# GyroDrive.net
KiCad netlist of a schematic drawn in EAGLE
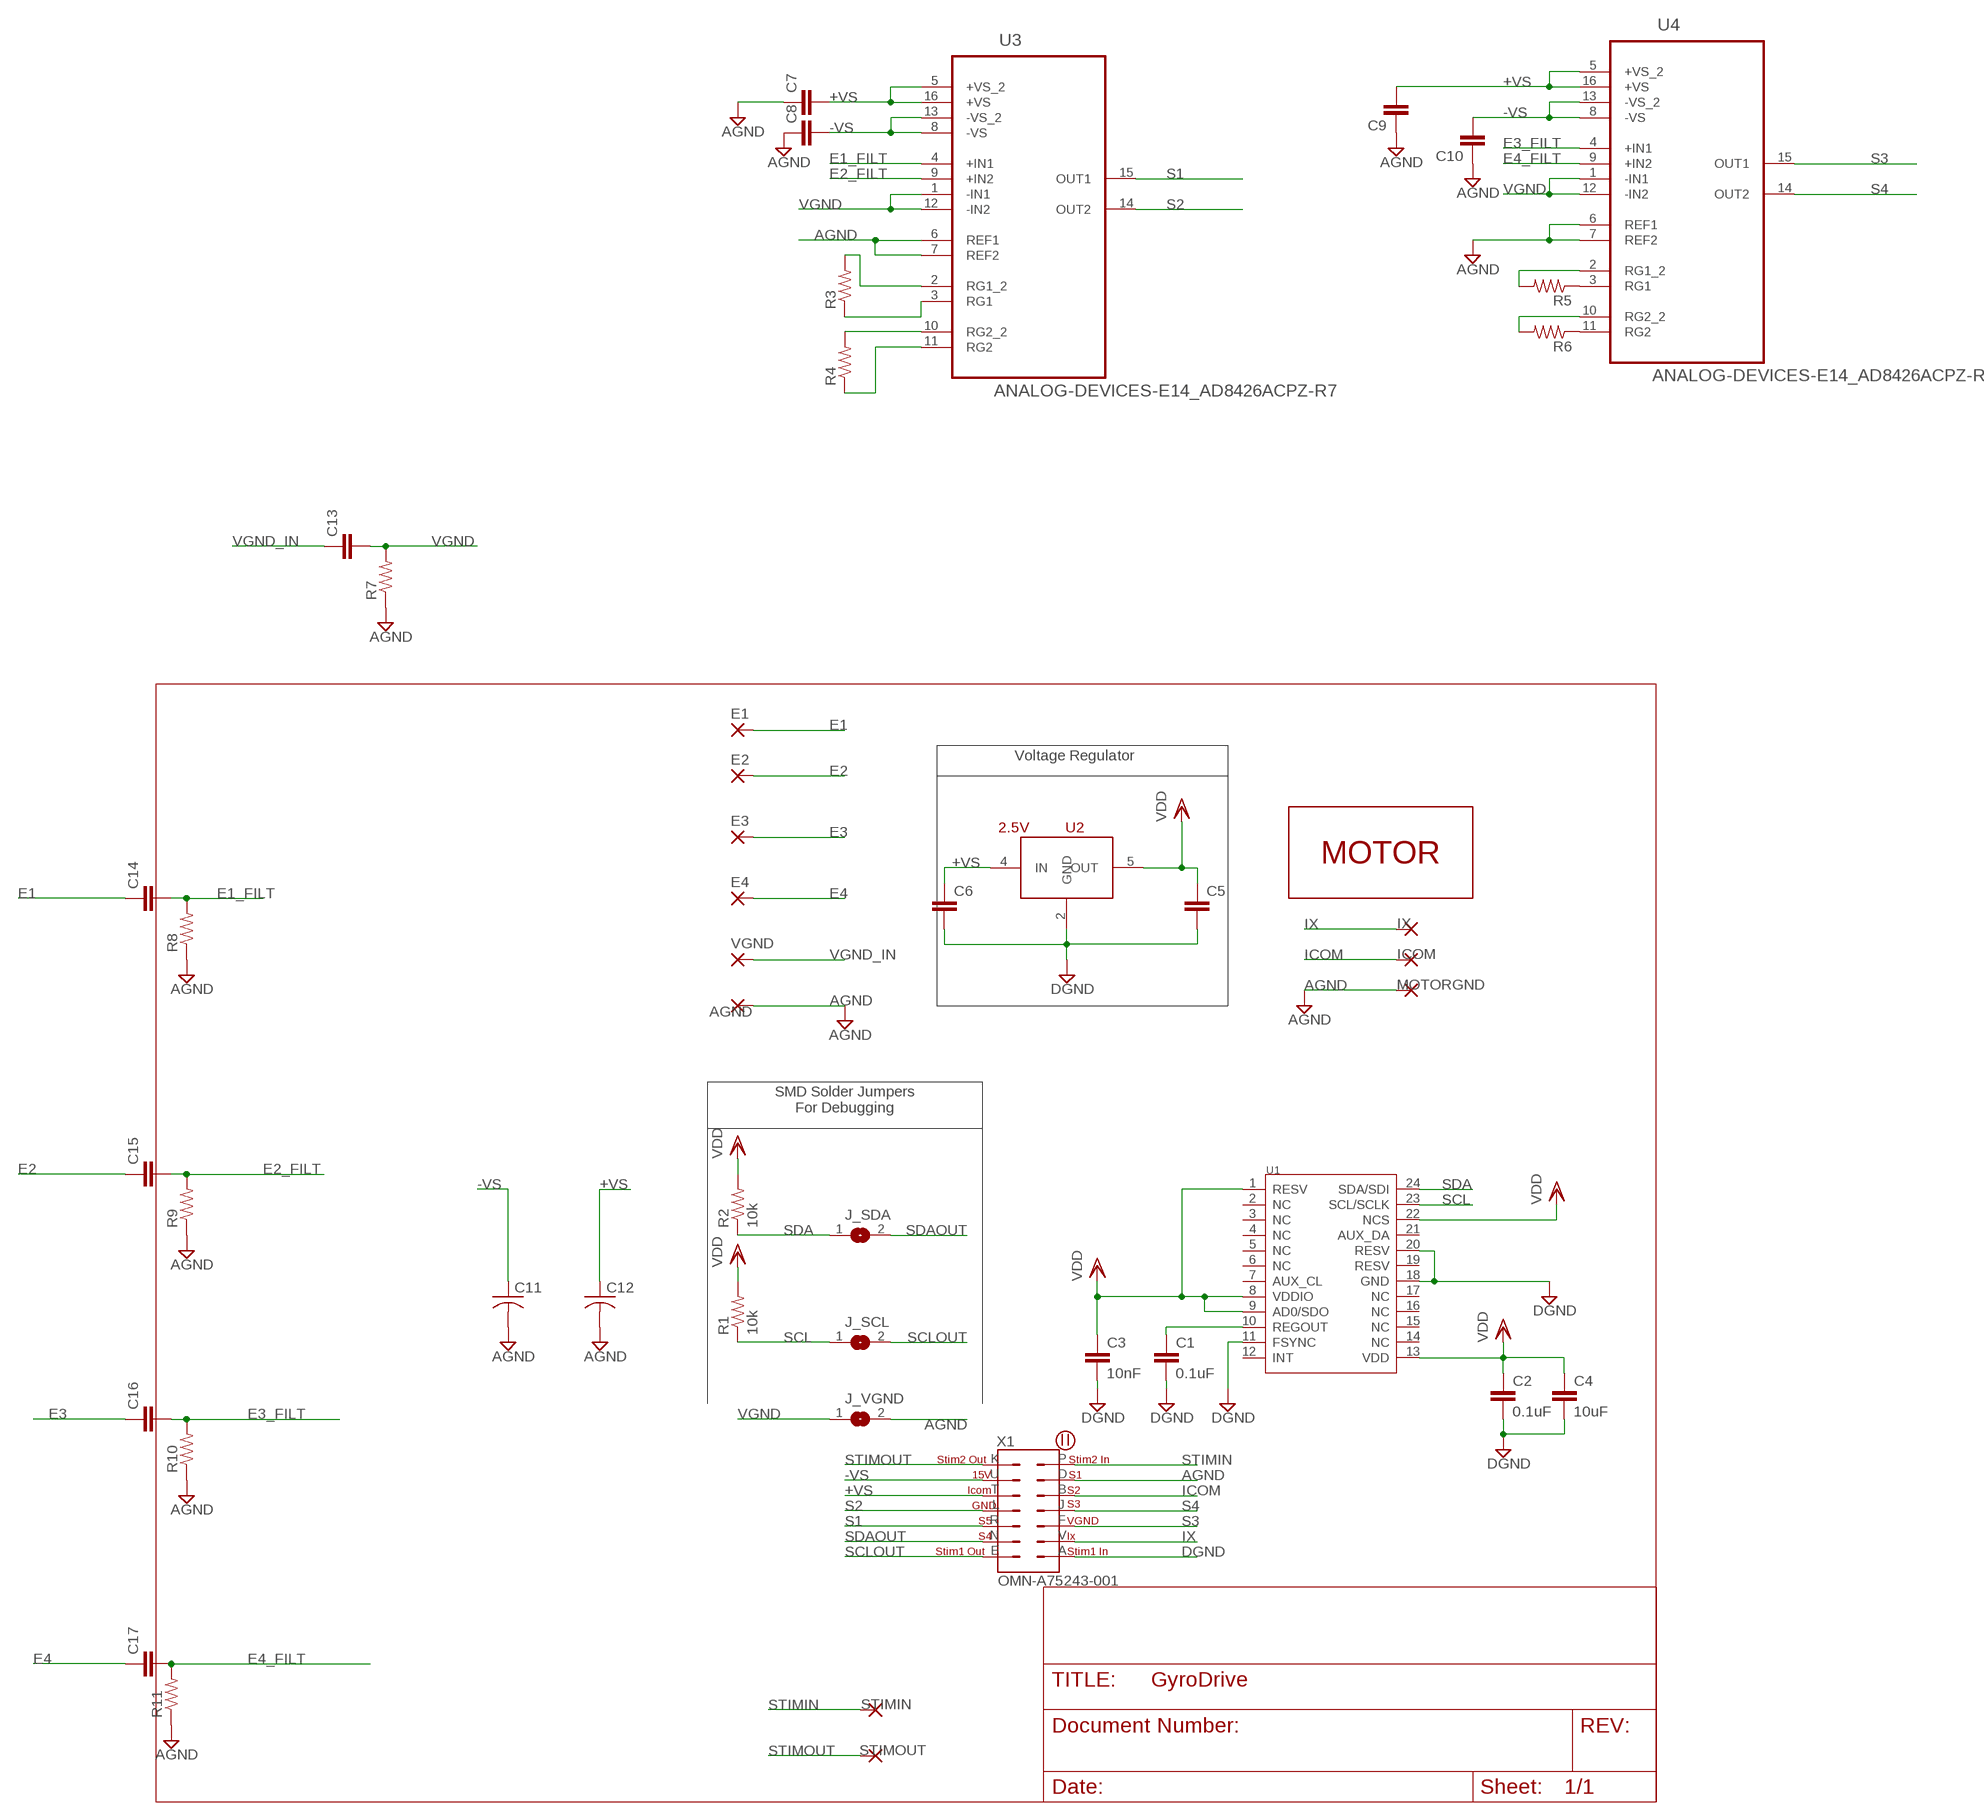
[diagram p0: schematic, sheet 1]

(export (version "E")
  (design (tool "Eeschema 10.0.6"))
  (components
    (comp (ref "AGND")
      (value "THROUGH-HOLE-30MIL/15MIL")
      (footprint "eagle-import:30MIL_15MIL")
      (libsource (lib "eagle-import") (part "THROUGH-HOLE-30MIL/15MIL"))
    )
    (comp (ref "C1")
      (value "0.1uF")
      (footprint "eagle-import:C0402")
      (libsource (lib "eagle-import") (part "C-EUC0402"))
    )
    (comp (ref "C2")
      (value "0.1uF")
      (footprint "eagle-import:C0402")
      (libsource (lib "eagle-import") (part "C-EUC0402"))
    )
    (comp (ref "C3")
      (value "10nF")
      (footprint "eagle-import:C0402")
      (libsource (lib "eagle-import") (part "C-EUC0402"))
    )
    (comp (ref "C4")
      (value "10uF")
      (footprint "eagle-import:C0603")
      (libsource (lib "eagle-import") (part "C-EUC0603"))
    )
    (comp (ref "C5")
      (value "C-EUC0402")
      (footprint "eagle-import:C0402")
      (libsource (lib "eagle-import") (part "C-EUC0402"))
    )
    (comp (ref "C6")
      (value "C-EUC0402")
      (footprint "eagle-import:C0402")
      (libsource (lib "eagle-import") (part "C-EUC0402"))
    )
    (comp (ref "C7")
      (value "C-EUC0201")
      (footprint "eagle-import:C0201")
      (libsource (lib "eagle-import") (part "C-EUC0201"))
    )
    (comp (ref "C8")
      (value "C-EUC0201")
      (footprint "eagle-import:C0201")
      (libsource (lib "eagle-import") (part "C-EUC0201"))
    )
    (comp (ref "C9")
      (value "C-EUC0201")
      (footprint "eagle-import:C0201")
      (libsource (lib "eagle-import") (part "C-EUC0201"))
    )
    (comp (ref "C10")
      (value "C-EUC0201")
      (footprint "eagle-import:C0201")
      (libsource (lib "eagle-import") (part "C-EUC0201"))
    )
    (comp (ref "C11")
      (value "C-USC0603")
      (footprint "eagle-import:C0603")
      (libsource (lib "eagle-import") (part "C-USC0603"))
    )
    (comp (ref "C12")
      (value "C-USC0603")
      (footprint "eagle-import:C0603")
      (libsource (lib "eagle-import") (part "C-USC0603"))
    )
    (comp (ref "C13")
      (value "C-EUC0201")
      (footprint "eagle-import:C0201")
      (libsource (lib "eagle-import") (part "C-EUC0201"))
    )
    (comp (ref "C14")
      (value "C-EUC0201")
      (footprint "eagle-import:C0201")
      (libsource (lib "eagle-import") (part "C-EUC0201"))
    )
    (comp (ref "C15")
      (value "C-EUC0201")
      (footprint "eagle-import:C0201")
      (libsource (lib "eagle-import") (part "C-EUC0201"))
    )
    (comp (ref "C16")
      (value "C-EUC0201")
      (footprint "eagle-import:C0201")
      (libsource (lib "eagle-import") (part "C-EUC0201"))
    )
    (comp (ref "C17")
      (value "C-EUC0201")
      (footprint "eagle-import:C0201")
      (libsource (lib "eagle-import") (part "C-EUC0201"))
    )
    (comp (ref "E1")
      (value "SMD25-25-MIL")
      (footprint "eagle-import:SMD25-25-MIL")
      (libsource (lib "eagle-import") (part "SMD25-25-MIL"))
    )
    (comp (ref "E2")
      (value "SMD25-25-MIL")
      (footprint "eagle-import:SMD25-25-MIL")
      (libsource (lib "eagle-import") (part "SMD25-25-MIL"))
    )
    (comp (ref "E3")
      (value "SMD25-25-MIL")
      (footprint "eagle-import:SMD25-25-MIL")
      (libsource (lib "eagle-import") (part "SMD25-25-MIL"))
    )
    (comp (ref "E4")
      (value "SMD25-25-MIL")
      (footprint "eagle-import:SMD25-25-MIL")
      (libsource (lib "eagle-import") (part "SMD25-25-MIL"))
    )
    (comp (ref "ICOM")
      (value "THROUGH-HOLE-30MIL/15MIL")
      (footprint "eagle-import:30MIL_15MIL")
      (libsource (lib "eagle-import") (part "THROUGH-HOLE-30MIL/15MIL"))
    )
    (comp (ref "IX")
      (value "THROUGH-HOLE-30MIL/15MIL")
      (footprint "eagle-import:30MIL_15MIL")
      (libsource (lib "eagle-import") (part "THROUGH-HOLE-30MIL/15MIL"))
    )
    (comp (ref "J_SCL")
      (value "SJ")
      (footprint "eagle-import:SJ")
      (libsource (lib "eagle-import") (part "SJ"))
    )
    (comp (ref "J_SDA")
      (value "SJ")
      (footprint "eagle-import:SJ")
      (libsource (lib "eagle-import") (part "SJ"))
    )
    (comp (ref "J_VGND")
      (value "SJ")
      (footprint "eagle-import:SJ")
      (libsource (lib "eagle-import") (part "SJ"))
    )
    (comp (ref "MOTORGND")
      (value "THROUGH-HOLE-30MIL/15MIL")
      (footprint "eagle-import:30MIL_15MIL")
      (libsource (lib "eagle-import") (part "THROUGH-HOLE-30MIL/15MIL"))
    )
    (comp (ref "R1")
      (value "10k")
      (footprint "eagle-import:R0201")
      (libsource (lib "eagle-import") (part "R-US_R0201"))
    )
    (comp (ref "R2")
      (value "10k")
      (footprint "eagle-import:R0201")
      (libsource (lib "eagle-import") (part "R-US_R0201"))
    )
    (comp (ref "R3")
      (value "R-US_R0201")
      (footprint "eagle-import:R0201")
      (libsource (lib "eagle-import") (part "R-US_R0201"))
    )
    (comp (ref "R4")
      (value "R-US_R0201")
      (footprint "eagle-import:R0201")
      (libsource (lib "eagle-import") (part "R-US_R0201"))
    )
    (comp (ref "R5")
      (value "R-US_R0201")
      (footprint "eagle-import:R0201")
      (libsource (lib "eagle-import") (part "R-US_R0201"))
    )
    (comp (ref "R6")
      (value "R-US_R0201")
      (footprint "eagle-import:R0201")
      (libsource (lib "eagle-import") (part "R-US_R0201"))
    )
    (comp (ref "R7")
      (value "R-US_R0201")
      (footprint "eagle-import:R0201")
      (libsource (lib "eagle-import") (part "R-US_R0201"))
    )
    (comp (ref "R8")
      (value "R-US_R0201")
      (footprint "eagle-import:R0201")
      (libsource (lib "eagle-import") (part "R-US_R0201"))
    )
    (comp (ref "R9")
      (value "R-US_R0201")
      (footprint "eagle-import:R0201")
      (libsource (lib "eagle-import") (part "R-US_R0201"))
    )
    (comp (ref "R10")
      (value "R-US_R0201")
      (footprint "eagle-import:R0201")
      (libsource (lib "eagle-import") (part "R-US_R0201"))
    )
    (comp (ref "R11")
      (value "R-US_R0201")
      (footprint "eagle-import:R0201")
      (libsource (lib "eagle-import") (part "R-US_R0201"))
    )
    (comp (ref "STIMIN")
      (value "THROUGH-HOLE-30MIL/15MIL")
      (footprint "eagle-import:30MIL_15MIL")
      (libsource (lib "eagle-import") (part "THROUGH-HOLE-30MIL/15MIL"))
    )
    (comp (ref "STIMOUT")
      (value "THROUGH-HOLE-30MIL/15MIL")
      (footprint "eagle-import:30MIL_15MIL")
      (libsource (lib "eagle-import") (part "THROUGH-HOLE-30MIL/15MIL"))
    )
    (comp (ref "U$2")
      (value "MICRODRIVE-MOTOR")
      (footprint "eagle-import:0206A001B-021-47_1-Y2825")
      (libsource (lib "eagle-import") (part "MICRODRIVE-MOTOR"))
    )
    (comp (ref "U1")
      (value "MPU-9250")
      (footprint "eagle-import:LEAD-QFN24")
      (libsource (lib "eagle-import") (part "MPU-9250"))
    )
    (comp (ref "U2")
      (value "2.5V")
      (footprint "eagle-import:SC70")
      (libsource (lib "eagle-import") (part "TPS715-FIXED"))
    )
    (comp (ref "U3")
      (value "ANALOG-DEVICES-E14_AD8426ACPZ-R7")
      (footprint "eagle-import:ANALOG-DEVICES-E14_QFN65P400X400X100-16N")
      (fields (field (name "MPN") "AD8426ACPZ-R7"))
      (libsource (lib "eagle-import") (part "ANALOG-DEVICES-E14_AD8426ACPZ-R7"))
    )
    (comp (ref "U4")
      (value "ANALOG-DEVICES-E14_AD8426ACPZ-R7")
      (footprint "eagle-import:ANALOG-DEVICES-E14_QFN65P400X400X100-16N")
      (fields (field (name "MPN") "AD8426ACPZ-R7"))
      (libsource (lib "eagle-import") (part "ANALOG-DEVICES-E14_AD8426ACPZ-R7"))
    )
    (comp (ref "VGND")
      (value "SMD25-25-MIL")
      (footprint "eagle-import:SMD25-25-MIL")
      (libsource (lib "eagle-import") (part "SMD25-25-MIL"))
    )
    (comp (ref "X1")
      (value "OMN-A75243-001")
      (footprint "eagle-import:OMN-A75243-001")
      (libsource (lib "eagle-import") (part "OMN-A75243-001"))
    )
  )
  (nets
    (net (code "1") (name "/+VS") (class "Default")
      (node (ref "C12") (pin "1") (pinfunction "1_1") (pintype "passive"))
      (node (ref "C6") (pin "1") (pinfunction "1_1") (pintype "passive"))
      (node (ref "C7") (pin "2") (pinfunction "2_2") (pintype "passive"))
      (node (ref "C9") (pin "2") (pinfunction "2_2") (pintype "passive"))
      (node (ref "U2") (pin "4") (pinfunction "IN_4") (pintype "bidirectional"))
      (node (ref "U3") (pin "16") (pinfunction "+VS_16") (pintype "passive"))
      (node (ref "U3") (pin "5") (pinfunction "+VS_2_5") (pintype "passive"))
      (node (ref "U4") (pin "16") (pinfunction "+VS_16") (pintype "passive"))
      (node (ref "U4") (pin "5") (pinfunction "+VS_2_5") (pintype "passive"))
      (node (ref "X1") (pin "T") (pinfunction "T_T") (pintype "passive"))
    )
    (net (code "2") (name "/-VS") (class "Default")
      (node (ref "C10") (pin "2") (pinfunction "2_2") (pintype "passive"))
      (node (ref "C11") (pin "1") (pinfunction "1_1") (pintype "passive"))
      (node (ref "C8") (pin "2") (pinfunction "2_2") (pintype "passive"))
      (node (ref "U3") (pin "13") (pinfunction "-VS_2_13") (pintype "passive"))
      (node (ref "U3") (pin "8") (pinfunction "-VS_8") (pintype "passive"))
      (node (ref "U4") (pin "13") (pinfunction "-VS_2_13") (pintype "passive"))
      (node (ref "U4") (pin "8") (pinfunction "-VS_8") (pintype "passive"))
      (node (ref "X1") (pin "U") (pinfunction "U_U") (pintype "passive"))
    )
    (net (code "3") (name "/E1") (class "Default")
      (node (ref "C14") (pin "1") (pinfunction "1_1") (pintype "passive"))
      (node (ref "E1") (pin "1") (pinfunction "P_1") (pintype "passive"))
    )
    (net (code "4") (name "/E1_FILT") (class "Default")
      (node (ref "C14") (pin "2") (pinfunction "2_2") (pintype "passive"))
      (node (ref "R8") (pin "2") (pinfunction "2_2") (pintype "passive"))
      (node (ref "U3") (pin "4") (pinfunction "+IN1_4") (pintype "passive"))
    )
    (net (code "5") (name "/E2") (class "Default")
      (node (ref "C15") (pin "1") (pinfunction "1_1") (pintype "passive"))
      (node (ref "E2") (pin "1") (pinfunction "P_1") (pintype "passive"))
    )
    (net (code "6") (name "/E2_FILT") (class "Default")
      (node (ref "C15") (pin "2") (pinfunction "2_2") (pintype "passive"))
      (node (ref "R9") (pin "2") (pinfunction "2_2") (pintype "passive"))
      (node (ref "U3") (pin "9") (pinfunction "+IN2_9") (pintype "passive"))
    )
    (net (code "7") (name "/E3") (class "Default")
      (node (ref "C16") (pin "1") (pinfunction "1_1") (pintype "passive"))
      (node (ref "E3") (pin "1") (pinfunction "P_1") (pintype "passive"))
    )
    (net (code "8") (name "/E3_FILT") (class "Default")
      (node (ref "C16") (pin "2") (pinfunction "2_2") (pintype "passive"))
      (node (ref "R10") (pin "2") (pinfunction "2_2") (pintype "passive"))
      (node (ref "U4") (pin "4") (pinfunction "+IN1_4") (pintype "passive"))
    )
    (net (code "9") (name "/E4") (class "Default")
      (node (ref "C17") (pin "1") (pinfunction "1_1") (pintype "passive"))
      (node (ref "E4") (pin "1") (pinfunction "P_1") (pintype "passive"))
    )
    (net (code "10") (name "/E4_FILT") (class "Default")
      (node (ref "C17") (pin "2") (pinfunction "2_2") (pintype "passive"))
      (node (ref "R11") (pin "2") (pinfunction "2_2") (pintype "passive"))
      (node (ref "U4") (pin "9") (pinfunction "+IN2_9") (pintype "passive"))
    )
    (net (code "11") (name "/ICOM") (class "Default")
      (node (ref "ICOM") (pin "P$1") (pinfunction "P_P$1") (pintype "passive"))
      (node (ref "X1") (pin "B") (pinfunction "B_B") (pintype "passive"))
    )
    (net (code "12") (name "/IX") (class "Default")
      (node (ref "IX") (pin "P$1") (pinfunction "P_P$1") (pintype "passive"))
      (node (ref "X1") (pin "V") (pinfunction "V_V") (pintype "passive"))
    )
    (net (code "13") (name "/S1") (class "Default")
      (node (ref "U3") (pin "15") (pinfunction "OUT1_15") (pintype "passive"))
      (node (ref "X1") (pin "R") (pinfunction "R_R") (pintype "passive"))
    )
    (net (code "14") (name "/S2") (class "Default")
      (node (ref "U3") (pin "14") (pinfunction "OUT2_14") (pintype "passive"))
      (node (ref "X1") (pin "L") (pinfunction "L_L") (pintype "passive"))
    )
    (net (code "15") (name "/S3") (class "Default")
      (node (ref "U4") (pin "15") (pinfunction "OUT1_15") (pintype "passive"))
      (node (ref "X1") (pin "F") (pinfunction "F_F") (pintype "passive"))
    )
    (net (code "16") (name "/S4") (class "Default")
      (node (ref "U4") (pin "14") (pinfunction "OUT2_14") (pintype "passive"))
      (node (ref "X1") (pin "J") (pinfunction "J_J") (pintype "passive"))
    )
    (net (code "17") (name "/SCL") (class "Default")
      (node (ref "J_SCL") (pin "1") (pinfunction "1_1") (pintype "passive"))
      (node (ref "R1") (pin "1") (pinfunction "1_1") (pintype "passive"))
      (node (ref "U1") (pin "23") (pinfunction "SCL/SCLK_23") (pintype "bidirectional"))
    )
    (net (code "18") (name "/SCLOUT") (class "Default")
      (node (ref "J_SCL") (pin "2") (pinfunction "2_2") (pintype "passive"))
      (node (ref "X1") (pin "E") (pinfunction "E_E") (pintype "passive"))
    )
    (net (code "19") (name "/SDA") (class "Default")
      (node (ref "J_SDA") (pin "1") (pinfunction "1_1") (pintype "passive"))
      (node (ref "R2") (pin "1") (pinfunction "1_1") (pintype "passive"))
      (node (ref "U1") (pin "24") (pinfunction "SDA/SDI_24") (pintype "bidirectional"))
    )
    (net (code "20") (name "/SDAOUT") (class "Default")
      (node (ref "J_SDA") (pin "2") (pinfunction "2_2") (pintype "passive"))
      (node (ref "X1") (pin "N") (pinfunction "N_N") (pintype "passive"))
    )
    (net (code "21") (name "/STIMIN") (class "Default")
      (node (ref "STIMIN") (pin "P$1") (pinfunction "P_P$1") (pintype "passive"))
      (node (ref "X1") (pin "P") (pinfunction "P_P") (pintype "passive"))
    )
    (net (code "22") (name "/STIMOUT") (class "Default")
      (node (ref "STIMOUT") (pin "P$1") (pinfunction "P_P$1") (pintype "passive"))
      (node (ref "X1") (pin "K") (pinfunction "K_K") (pintype "passive"))
    )
    (net (code "23") (name "/VGND") (class "Default")
      (node (ref "C13") (pin "2") (pinfunction "2_2") (pintype "passive"))
      (node (ref "J_VGND") (pin "1") (pinfunction "1_1") (pintype "passive"))
      (node (ref "R7") (pin "2") (pinfunction "2_2") (pintype "passive"))
      (node (ref "U3") (pin "1") (pinfunction "-IN1_1") (pintype "passive"))
      (node (ref "U3") (pin "12") (pinfunction "-IN2_12") (pintype "passive"))
      (node (ref "U4") (pin "1") (pinfunction "-IN1_1") (pintype "passive"))
      (node (ref "U4") (pin "12") (pinfunction "-IN2_12") (pintype "passive"))
    )
    (net (code "24") (name "/VGND_IN") (class "Default")
      (node (ref "C13") (pin "1") (pinfunction "1_1") (pintype "passive"))
      (node (ref "VGND") (pin "1") (pinfunction "P_1") (pintype "passive"))
    )
    (net (code "25") (name "AGND") (class "Default")
      (node (ref "AGND") (pin "P$1") (pinfunction "P_P$1") (pintype "passive"))
      (node (ref "C10") (pin "1") (pinfunction "1_1") (pintype "passive"))
      (node (ref "C11") (pin "2") (pinfunction "2_2") (pintype "passive"))
      (node (ref "C12") (pin "2") (pinfunction "2_2") (pintype "passive"))
      (node (ref "C7") (pin "1") (pinfunction "1_1") (pintype "passive"))
      (node (ref "C8") (pin "1") (pinfunction "1_1") (pintype "passive"))
      (node (ref "C9") (pin "1") (pinfunction "1_1") (pintype "passive"))
      (node (ref "J_VGND") (pin "2") (pinfunction "2_2") (pintype "passive"))
      (node (ref "MOTORGND") (pin "P$1") (pinfunction "P_P$1") (pintype "passive"))
      (node (ref "R10") (pin "1") (pinfunction "1_1") (pintype "passive"))
      (node (ref "R11") (pin "1") (pinfunction "1_1") (pintype "passive"))
      (node (ref "R7") (pin "1") (pinfunction "1_1") (pintype "passive"))
      (node (ref "R8") (pin "1") (pinfunction "1_1") (pintype "passive"))
      (node (ref "R9") (pin "1") (pinfunction "1_1") (pintype "passive"))
      (node (ref "U3") (pin "6") (pinfunction "REF1_6") (pintype "passive"))
      (node (ref "U3") (pin "7") (pinfunction "REF2_7") (pintype "passive"))
      (node (ref "U4") (pin "6") (pinfunction "REF1_6") (pintype "passive"))
      (node (ref "U4") (pin "7") (pinfunction "REF2_7") (pintype "passive"))
      (node (ref "X1") (pin "D") (pinfunction "D_D") (pintype "passive"))
    )
    (net (code "26") (name "DGND") (class "Default")
      (node (ref "C1") (pin "2") (pinfunction "2_2") (pintype "passive"))
      (node (ref "C2") (pin "2") (pinfunction "2_2") (pintype "passive"))
      (node (ref "C3") (pin "2") (pinfunction "2_2") (pintype "passive"))
      (node (ref "C4") (pin "2") (pinfunction "2_2") (pintype "passive"))
      (node (ref "C5") (pin "2") (pinfunction "2_2") (pintype "passive"))
      (node (ref "C6") (pin "2") (pinfunction "2_2") (pintype "passive"))
      (node (ref "U1") (pin "11") (pinfunction "FSYNC_11") (pintype "bidirectional"))
      (node (ref "U1") (pin "18") (pinfunction "GND_18") (pintype "bidirectional"))
      (node (ref "U1") (pin "20") (pinfunction "RESV_20") (pintype "bidirectional"))
      (node (ref "U2") (pin "2") (pinfunction "GND_2") (pintype "bidirectional"))
      (node (ref "X1") (pin "A") (pinfunction "A_A") (pintype "passive"))
    )
    (net (code "27") (name "Net-(U1-REGOUT)") (class "Default")
      (node (ref "C1") (pin "1") (pinfunction "1_1") (pintype "passive"))
      (node (ref "U1") (pin "10") (pinfunction "REGOUT_10") (pintype "bidirectional"))
    )
    (net (code "28") (name "Net-(U3-RG1)") (class "Default")
      (node (ref "R3") (pin "1") (pinfunction "1_1") (pintype "passive"))
      (node (ref "U3") (pin "3") (pinfunction "RG1_3") (pintype "passive"))
    )
    (net (code "29") (name "Net-(U3-RG1_2)") (class "Default")
      (node (ref "R3") (pin "2") (pinfunction "2_2") (pintype "passive"))
      (node (ref "U3") (pin "2") (pinfunction "RG1_2_2") (pintype "passive"))
    )
    (net (code "30") (name "Net-(U3-RG2)") (class "Default")
      (node (ref "R4") (pin "1") (pinfunction "1_1") (pintype "passive"))
      (node (ref "U3") (pin "11") (pinfunction "RG2_11") (pintype "passive"))
    )
    (net (code "31") (name "Net-(U3-RG2_2)") (class "Default")
      (node (ref "R4") (pin "2") (pinfunction "2_2") (pintype "passive"))
      (node (ref "U3") (pin "10") (pinfunction "RG2_2_10") (pintype "passive"))
    )
    (net (code "32") (name "Net-(U4-RG1)") (class "Default")
      (node (ref "R5") (pin "1") (pinfunction "1_1") (pintype "passive"))
      (node (ref "U4") (pin "3") (pinfunction "RG1_3") (pintype "passive"))
    )
    (net (code "33") (name "Net-(U4-RG1_2)") (class "Default")
      (node (ref "R5") (pin "2") (pinfunction "2_2") (pintype "passive"))
      (node (ref "U4") (pin "2") (pinfunction "RG1_2_2") (pintype "passive"))
    )
    (net (code "34") (name "Net-(U4-RG2)") (class "Default")
      (node (ref "R6") (pin "1") (pinfunction "1_1") (pintype "passive"))
      (node (ref "U4") (pin "11") (pinfunction "RG2_11") (pintype "passive"))
    )
    (net (code "35") (name "Net-(U4-RG2_2)") (class "Default")
      (node (ref "R6") (pin "2") (pinfunction "2_2") (pintype "passive"))
      (node (ref "U4") (pin "10") (pinfunction "RG2_2_10") (pintype "passive"))
    )
    (net (code "36") (name "VDD") (class "Default")
      (node (ref "C2") (pin "1") (pinfunction "1_1") (pintype "passive"))
      (node (ref "C3") (pin "1") (pinfunction "1_1") (pintype "passive"))
      (node (ref "C4") (pin "1") (pinfunction "1_1") (pintype "passive"))
      (node (ref "C5") (pin "1") (pinfunction "1_1") (pintype "passive"))
      (node (ref "R1") (pin "2") (pinfunction "2_2") (pintype "passive"))
      (node (ref "R2") (pin "2") (pinfunction "2_2") (pintype "passive"))
      (node (ref "U1") (pin "1") (pinfunction "RESV_1") (pintype "bidirectional"))
      (node (ref "U1") (pin "13") (pinfunction "VDD_13") (pintype "bidirectional"))
      (node (ref "U1") (pin "22") (pinfunction "NCS_22") (pintype "bidirectional"))
      (node (ref "U1") (pin "8") (pinfunction "VDDIO_8") (pintype "bidirectional"))
      (node (ref "U1") (pin "9") (pinfunction "AD0/SDO_9") (pintype "bidirectional"))
      (node (ref "U2") (pin "5") (pinfunction "OUT_5") (pintype "bidirectional"))
    )
    (net (code "37") (name "unconnected-(U1-AUX_CL-Pad7)") (class "Default")
      (node (ref "U1") (pin "7") (pinfunction "AUX_CL_7") (pintype "bidirectional"))
    )
    (net (code "38") (name "unconnected-(U1-AUX_DA-Pad21)") (class "Default")
      (node (ref "U1") (pin "21") (pinfunction "AUX_DA_21") (pintype "bidirectional"))
    )
    (net (code "39") (name "unconnected-(U1-INT-Pad12)") (class "Default")
      (node (ref "U1") (pin "12") (pinfunction "INT_12") (pintype "bidirectional"))
    )
    (net (code "40") (name "unconnected-(U1-NC-Pad2)") (class "Default")
      (node (ref "U1") (pin "2") (pinfunction "NC_2") (pintype "bidirectional"))
    )
    (net (code "41") (name "unconnected-(U1-NC-Pad3)") (class "Default")
      (node (ref "U1") (pin "3") (pinfunction "NC_3") (pintype "bidirectional"))
    )
    (net (code "42") (name "unconnected-(U1-NC-Pad4)") (class "Default")
      (node (ref "U1") (pin "4") (pinfunction "NC_4") (pintype "bidirectional"))
    )
    (net (code "43") (name "unconnected-(U1-NC-Pad5)") (class "Default")
      (node (ref "U1") (pin "5") (pinfunction "NC_5") (pintype "bidirectional"))
    )
    (net (code "44") (name "unconnected-(U1-NC-Pad6)") (class "Default")
      (node (ref "U1") (pin "6") (pinfunction "NC_6") (pintype "bidirectional"))
    )
    (net (code "45") (name "unconnected-(U1-NC-Pad14)") (class "Default")
      (node (ref "U1") (pin "14") (pinfunction "NC_14") (pintype "bidirectional"))
    )
    (net (code "46") (name "unconnected-(U1-NC-Pad15)") (class "Default")
      (node (ref "U1") (pin "15") (pinfunction "NC_15") (pintype "bidirectional"))
    )
    (net (code "47") (name "unconnected-(U1-NC-Pad16)") (class "Default")
      (node (ref "U1") (pin "16") (pinfunction "NC_16") (pintype "bidirectional"))
    )
    (net (code "48") (name "unconnected-(U1-NC-Pad17)") (class "Default")
      (node (ref "U1") (pin "17") (pinfunction "NC_17") (pintype "bidirectional"))
    )
    (net (code "49") (name "unconnected-(U1-RESV-Pad19)") (class "Default")
      (node (ref "U1") (pin "19") (pinfunction "RESV_19") (pintype "bidirectional"))
    )
  )
)
